# mcu.net
KiCad netlist of a schematic drawn in Altium Designer
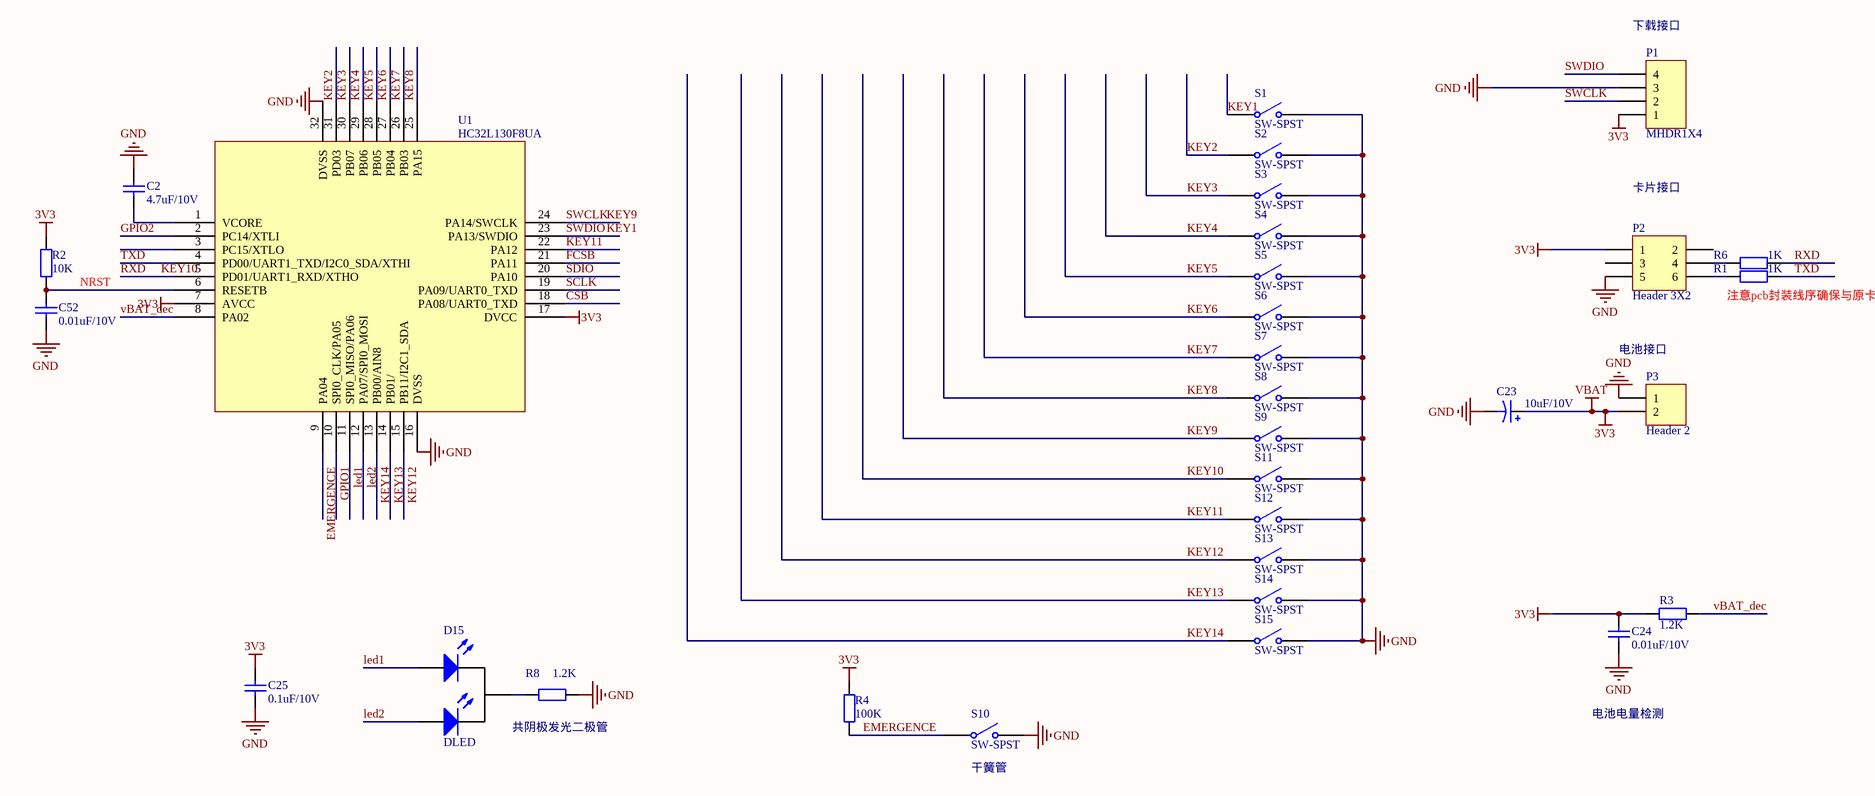
[diagram p0: mcu.SchDoc]

(export (version "E")
  (design (tool "Eeschema 10.0.6"))
  (components
    (comp (ref "C2")
      (value "4.7uF/10V")
      (footprint "0603C")
      (description "Capacitor")
      (fields (field (name "PUBLISHER") "Altium Limited"))
      (libsource (lib "Miscellaneous Devices") (part "Cap"))
    )
    (comp (ref "C23")
      (value "10uF/10V")
      (description "Polarized Capacitor (Radial)")
      (fields (field (name "PUBLISHER") "Altium Limited"))
      (libsource (lib "Miscellaneous Devices") (part "Cap Pol1"))
    )
    (comp (ref "C24")
      (value "0.01uF/10V")
      (footprint "0603C")
      (description "Capacitor")
      (fields (field (name "PUBLISHER") "Altium Limited"))
      (libsource (lib "Miscellaneous Devices") (part "Cap"))
    )
    (comp (ref "C25")
      (value "0.1uF/10V")
      (footprint "0603C")
      (description "Capacitor")
      (fields (field (name "PUBLISHER") "Altium Limited"))
      (libsource (lib "Miscellaneous Devices") (part "Cap"))
    )
    (comp (ref "C52")
      (value "0.01uF/10V")
      (footprint "0603C")
      (description "Capacitor")
      (fields (field (name "PUBLISHER") "Altium Limited"))
      (libsource (lib "Miscellaneous Devices") (part "Cap"))
    )
    (comp (ref "D15") (value "DLED") (libsource (lib "Schlib_20110825") (part "DLED")))
    (comp (ref "P1")
      (value "MHDR1X4")
      (footprint "SIP4")
      (description "Header, 4-Pin")
      (fields (field (name "PUBLISHER") "Altium Limited"))
      (libsource (lib "Miscellaneous Connectors") (part "MHDR1X4"))
    )
    (comp (ref "P2")
      (value "Header 3X2")
      (description "Header, 3-Pin, Dual row")
      (fields (field (name "PUBLISHER") "Altium Limited"))
      (libsource (lib "Miscellaneous Connectors") (part "Header 3X2"))
    )
    (comp (ref "P3")
      (value "Header 2")
      (description "Header, 2-Pin")
      (fields (field (name "PUBLISHER") "Altium Limited"))
      (libsource (lib "Miscellaneous Connectors") (part "Header 2"))
    )
    (comp (ref "R1")
      (value "1K")
      (footprint "0603R")
      (description "Resistor")
      (fields (field (name "PUBLISHER") "Altium Limited"))
      (libsource (lib "Miscellaneous Devices") (part "Res2"))
    )
    (comp (ref "R2")
      (value "10K")
      (footprint "0603R")
      (description "Resistor")
      (fields (field (name "PUBLISHER") "Altium Limited"))
      (libsource (lib "") (part "Res2_2"))
    )
    (comp (ref "R3")
      (value "1.2K")
      (footprint "0603R")
      (description "Resistor")
      (fields (field (name "PUBLISHER") "Altium Limited"))
      (libsource (lib "Miscellaneous Devices") (part "Res2"))
    )
    (comp (ref "R4")
      (value "100K")
      (footprint "0603R")
      (description "Resistor")
      (fields (field (name "PUBLISHER") "Altium Limited"))
      (libsource (lib "") (part "Res2_1"))
    )
    (comp (ref "R6")
      (value "1K")
      (footprint "0603R")
      (description "Resistor")
      (fields (field (name "PUBLISHER") "Altium Limited"))
      (libsource (lib "Miscellaneous Devices") (part "Res2"))
    )
    (comp (ref "R8")
      (value "1.2K")
      (footprint "0603R")
      (description "Resistor")
      (fields (field (name "PUBLISHER") "Altium Limited"))
      (libsource (lib "Miscellaneous Devices") (part "Res2"))
    )
    (comp (ref "S1")
      (value "SW-SPST")
      (description "Single-Pole, Single-Throw Switch")
      (fields (field (name "PUBLISHER") "Altium Limited"))
      (libsource (lib "Miscellaneous Devices") (part "SW-SPST"))
    )
    (comp (ref "S2")
      (value "SW-SPST")
      (description "Single-Pole, Single-Throw Switch")
      (fields (field (name "PUBLISHER") "Altium Limited"))
      (libsource (lib "Miscellaneous Devices") (part "SW-SPST"))
    )
    (comp (ref "S3")
      (value "SW-SPST")
      (description "Single-Pole, Single-Throw Switch")
      (fields (field (name "PUBLISHER") "Altium Limited"))
      (libsource (lib "Miscellaneous Devices") (part "SW-SPST"))
    )
    (comp (ref "S4")
      (value "SW-SPST")
      (description "Single-Pole, Single-Throw Switch")
      (fields (field (name "PUBLISHER") "Altium Limited"))
      (libsource (lib "Miscellaneous Devices") (part "SW-SPST"))
    )
    (comp (ref "S5")
      (value "SW-SPST")
      (description "Single-Pole, Single-Throw Switch")
      (fields (field (name "PUBLISHER") "Altium Limited"))
      (libsource (lib "Miscellaneous Devices") (part "SW-SPST"))
    )
    (comp (ref "S6")
      (value "SW-SPST")
      (description "Single-Pole, Single-Throw Switch")
      (fields (field (name "PUBLISHER") "Altium Limited"))
      (libsource (lib "Miscellaneous Devices") (part "SW-SPST"))
    )
    (comp (ref "S7")
      (value "SW-SPST")
      (description "Single-Pole, Single-Throw Switch")
      (fields (field (name "PUBLISHER") "Altium Limited"))
      (libsource (lib "Miscellaneous Devices") (part "SW-SPST"))
    )
    (comp (ref "S8")
      (value "SW-SPST")
      (description "Single-Pole, Single-Throw Switch")
      (fields (field (name "PUBLISHER") "Altium Limited"))
      (libsource (lib "Miscellaneous Devices") (part "SW-SPST"))
    )
    (comp (ref "S9")
      (value "SW-SPST")
      (description "Single-Pole, Single-Throw Switch")
      (fields (field (name "PUBLISHER") "Altium Limited"))
      (libsource (lib "Miscellaneous Devices") (part "SW-SPST"))
    )
    (comp (ref "S10")
      (value "SW-SPST")
      (description "Single-Pole, Single-Throw Switch")
      (fields (field (name "PUBLISHER") "Altium Limited"))
      (libsource (lib "Miscellaneous Devices") (part "SW-SPST"))
    )
    (comp (ref "S11")
      (value "SW-SPST")
      (description "Single-Pole, Single-Throw Switch")
      (fields (field (name "PUBLISHER") "Altium Limited"))
      (libsource (lib "Miscellaneous Devices") (part "SW-SPST"))
    )
    (comp (ref "S12")
      (value "SW-SPST")
      (description "Single-Pole, Single-Throw Switch")
      (fields (field (name "PUBLISHER") "Altium Limited"))
      (libsource (lib "Miscellaneous Devices") (part "SW-SPST"))
    )
    (comp (ref "S13")
      (value "SW-SPST")
      (description "Single-Pole, Single-Throw Switch")
      (fields (field (name "PUBLISHER") "Altium Limited"))
      (libsource (lib "Miscellaneous Devices") (part "SW-SPST"))
    )
    (comp (ref "S14")
      (value "SW-SPST")
      (description "Single-Pole, Single-Throw Switch")
      (fields (field (name "PUBLISHER") "Altium Limited"))
      (libsource (lib "Miscellaneous Devices") (part "SW-SPST"))
    )
    (comp (ref "S15")
      (value "SW-SPST")
      (description "Single-Pole, Single-Throw Switch")
      (fields (field (name "PUBLISHER") "Altium Limited"))
      (libsource (lib "Miscellaneous Devices") (part "SW-SPST"))
    )
    (comp (ref "U1")
      (value "HC32L130F8UA")
      (footprint "QFN40P400X400X80-32N")
      (libsource (lib "Schlib_20110825") (part "HC32L130F8UA"))
    )
  )
  (nets
    (net (code "1") (name "/CSB") (class "Default")
      (node (ref "U1") (pin "18") (pinfunction "PA08/UART0_TXD_18") (pintype "passive"))
    )
    (net (code "2") (name "/EMERGENCE") (class "Default")
      (node (ref "R4") (pin "2") (pinfunction "2_2") (pintype "passive"))
      (node (ref "S10") (pin "1") (pinfunction "COMMON_1") (pintype "passive"))
      (node (ref "U1") (pin "9") (pinfunction "PA04_9") (pintype "passive"))
    )
    (net (code "3") (name "/FCSB") (class "Default")
      (node (ref "U1") (pin "21") (pinfunction "PA11_21") (pintype "passive"))
    )
    (net (code "4") (name "/GPIO1") (class "Default")
      (node (ref "U1") (pin "10") (pinfunction "SPI0_CLK/PA05_10") (pintype "passive"))
    )
    (net (code "5") (name "/GPIO2") (class "Default")
      (node (ref "U1") (pin "2") (pinfunction "PC14/XTLI_2") (pintype "passive"))
    )
    (net (code "6") (name "/KEY1") (class "Default")
      (node (ref "P1") (pin "4") (pinfunction "4_4") (pintype "passive"))
      (node (ref "S1") (pin "1") (pinfunction "COMMON_1") (pintype "passive"))
      (node (ref "U1") (pin "23") (pinfunction "PA13/SWDIO_23") (pintype "passive"))
    )
    (net (code "7") (name "/KEY2") (class "Default")
      (node (ref "S2") (pin "1") (pinfunction "COMMON_1") (pintype "passive"))
      (node (ref "U1") (pin "31") (pinfunction "PD03_31") (pintype "passive"))
    )
    (net (code "8") (name "/KEY3") (class "Default")
      (node (ref "S3") (pin "1") (pinfunction "COMMON_1") (pintype "passive"))
      (node (ref "U1") (pin "30") (pinfunction "PB07_30") (pintype "passive"))
    )
    (net (code "9") (name "/KEY4") (class "Default")
      (node (ref "S4") (pin "1") (pinfunction "COMMON_1") (pintype "passive"))
      (node (ref "U1") (pin "29") (pinfunction "PB06_29") (pintype "passive"))
    )
    (net (code "10") (name "/KEY5") (class "Default")
      (node (ref "S5") (pin "1") (pinfunction "COMMON_1") (pintype "passive"))
      (node (ref "U1") (pin "28") (pinfunction "PB05_28") (pintype "passive"))
    )
    (net (code "11") (name "/KEY6") (class "Default")
      (node (ref "S6") (pin "1") (pinfunction "COMMON_1") (pintype "passive"))
      (node (ref "U1") (pin "27") (pinfunction "PB04_27") (pintype "passive"))
    )
    (net (code "12") (name "/KEY7") (class "Default")
      (node (ref "S7") (pin "1") (pinfunction "COMMON_1") (pintype "passive"))
      (node (ref "U1") (pin "26") (pinfunction "PB03_26") (pintype "passive"))
    )
    (net (code "13") (name "/KEY8") (class "Default")
      (node (ref "S8") (pin "1") (pinfunction "COMMON_1") (pintype "passive"))
      (node (ref "U1") (pin "25") (pinfunction "PA15_25") (pintype "passive"))
    )
    (net (code "14") (name "/KEY9") (class "Default")
      (node (ref "P1") (pin "2") (pinfunction "2_2") (pintype "passive"))
      (node (ref "S9") (pin "1") (pinfunction "COMMON_1") (pintype "passive"))
      (node (ref "U1") (pin "24") (pinfunction "PA14/SWCLK_24") (pintype "passive"))
    )
    (net (code "15") (name "/KEY10") (class "Default")
      (node (ref "R6") (pin "1") (pinfunction "1_1") (pintype "passive"))
      (node (ref "S11") (pin "1") (pinfunction "COMMON_1") (pintype "passive"))
      (node (ref "U1") (pin "5") (pinfunction "PD01/UART1_RXD/XTHO_5") (pintype "passive"))
    )
    (net (code "16") (name "/KEY11") (class "Default")
      (node (ref "S12") (pin "1") (pinfunction "COMMON_1") (pintype "passive"))
      (node (ref "U1") (pin "22") (pinfunction "PA12_22") (pintype "passive"))
    )
    (net (code "17") (name "/KEY12") (class "Default")
      (node (ref "S13") (pin "1") (pinfunction "COMMON_1") (pintype "passive"))
      (node (ref "U1") (pin "15") (pinfunction "PB11/I2C1_SDA_15") (pintype "passive"))
    )
    (net (code "18") (name "/KEY13") (class "Default")
      (node (ref "S14") (pin "1") (pinfunction "COMMON_1") (pintype "passive"))
      (node (ref "U1") (pin "14") (pinfunction "PB01/_14") (pintype "passive"))
    )
    (net (code "19") (name "/KEY14") (class "Default")
      (node (ref "S15") (pin "1") (pinfunction "COMMON_1") (pintype "passive"))
      (node (ref "U1") (pin "13") (pinfunction "PB00/AIN8_13") (pintype "passive"))
    )
    (net (code "20") (name "/NRST") (class "Default")
      (node (ref "C52") (pin "1") (pinfunction "1_1") (pintype "passive"))
      (node (ref "R2") (pin "1") (pinfunction "1_1") (pintype "passive"))
      (node (ref "U1") (pin "6") (pinfunction "RESETB_6") (pintype "passive"))
    )
    (net (code "21") (name "/SCLK") (class "Default")
      (node (ref "U1") (pin "19") (pinfunction "PA09/UART0_TXD_19") (pintype "passive"))
    )
    (net (code "22") (name "/SDIO") (class "Default")
      (node (ref "U1") (pin "20") (pinfunction "PA10_20") (pintype "passive"))
    )
    (net (code "23") (name "/TXD") (class "Default")
      (node (ref "R1") (pin "1") (pinfunction "1_1") (pintype "passive"))
      (node (ref "U1") (pin "4") (pinfunction "PD00/UART1_TXD/I2C0_SDA/XTHI_4") (pintype "passive"))
    )
    (net (code "24") (name "/led1") (class "Default")
      (node (ref "D15") (pin "1") (pinfunction "A_1") (pintype "passive"))
      (node (ref "U1") (pin "11") (pinfunction "SPI0_MISO/PA06_11") (pintype "passive"))
    )
    (net (code "25") (name "/led2") (class "Default")
      (node (ref "D15") (pin "3") (pinfunction "A_3") (pintype "passive"))
      (node (ref "U1") (pin "12") (pinfunction "PA07/SPI0_MOSI_12") (pintype "passive"))
    )
    (net (code "26") (name "/vBAT_dec") (class "Default")
      (node (ref "R3") (pin "1") (pinfunction "1_1") (pintype "passive"))
      (node (ref "U1") (pin "8") (pinfunction "PA02_8") (pintype "passive"))
    )
    (net (code "27") (name "3V3") (class "Default")
      (node (ref "C23") (pin "1") (pinfunction "1_1") (pintype "passive"))
      (node (ref "C24") (pin "1") (pinfunction "1_1") (pintype "passive"))
      (node (ref "C25") (pin "1") (pinfunction "1_1") (pintype "passive"))
      (node (ref "P1") (pin "1") (pinfunction "1_1") (pintype "passive"))
      (node (ref "P2") (pin "1") (pinfunction "1_1") (pintype "passive"))
      (node (ref "P3") (pin "2") (pinfunction "2_2") (pintype "passive"))
      (node (ref "R2") (pin "2") (pinfunction "2_2") (pintype "passive"))
      (node (ref "R3") (pin "2") (pinfunction "2_2") (pintype "passive"))
      (node (ref "R4") (pin "1") (pinfunction "1_1") (pintype "passive"))
      (node (ref "U1") (pin "17") (pinfunction "DVCC_17") (pintype "passive"))
      (node (ref "U1") (pin "7") (pinfunction "AVCC_7") (pintype "passive"))
    )
    (net (code "28") (name "GND") (class "Default")
      (node (ref "C2") (pin "1") (pinfunction "1_1") (pintype "passive"))
      (node (ref "C23") (pin "2") (pinfunction "2_2") (pintype "passive"))
      (node (ref "C24") (pin "2") (pinfunction "2_2") (pintype "passive"))
      (node (ref "C25") (pin "2") (pinfunction "2_2") (pintype "passive"))
      (node (ref "C52") (pin "2") (pinfunction "2_2") (pintype "passive"))
      (node (ref "P1") (pin "3") (pinfunction "3_3") (pintype "passive"))
      (node (ref "P2") (pin "5") (pinfunction "5_5") (pintype "passive"))
      (node (ref "P3") (pin "1") (pinfunction "1_1") (pintype "passive"))
      (node (ref "R8") (pin "1") (pinfunction "1_1") (pintype "passive"))
      (node (ref "S1") (pin "2") (pinfunction "NO_2") (pintype "passive"))
      (node (ref "S10") (pin "2") (pinfunction "NO_2") (pintype "passive"))
      (node (ref "S11") (pin "2") (pinfunction "NO_2") (pintype "passive"))
      (node (ref "S12") (pin "2") (pinfunction "NO_2") (pintype "passive"))
      (node (ref "S13") (pin "2") (pinfunction "NO_2") (pintype "passive"))
      (node (ref "S14") (pin "2") (pinfunction "NO_2") (pintype "passive"))
      (node (ref "S15") (pin "2") (pinfunction "NO_2") (pintype "passive"))
      (node (ref "S2") (pin "2") (pinfunction "NO_2") (pintype "passive"))
      (node (ref "S3") (pin "2") (pinfunction "NO_2") (pintype "passive"))
      (node (ref "S4") (pin "2") (pinfunction "NO_2") (pintype "passive"))
      (node (ref "S5") (pin "2") (pinfunction "NO_2") (pintype "passive"))
      (node (ref "S6") (pin "2") (pinfunction "NO_2") (pintype "passive"))
      (node (ref "S7") (pin "2") (pinfunction "NO_2") (pintype "passive"))
      (node (ref "S8") (pin "2") (pinfunction "NO_2") (pintype "passive"))
      (node (ref "S9") (pin "2") (pinfunction "NO_2") (pintype "passive"))
      (node (ref "U1") (pin "16") (pinfunction "DVSS_16") (pintype "passive"))
      (node (ref "U1") (pin "32") (pinfunction "DVSS_32") (pintype "passive"))
    )
    (net (code "29") (name "Net-(D15-K)") (class "Default")
      (node (ref "D15") (pin "2") (pinfunction "K_2") (pintype "passive"))
      (node (ref "R8") (pin "2") (pinfunction "2_2") (pintype "passive"))
    )
    (net (code "30") (name "Net-(P2-Pad4)") (class "Default")
      (node (ref "P2") (pin "4") (pinfunction "4_4") (pintype "passive"))
      (node (ref "R6") (pin "2") (pinfunction "2_2") (pintype "passive"))
    )
    (net (code "31") (name "Net-(P2-Pad6)") (class "Default")
      (node (ref "P2") (pin "6") (pinfunction "6_6") (pintype "passive"))
      (node (ref "R1") (pin "2") (pinfunction "2_2") (pintype "passive"))
    )
    (net (code "32") (name "Net-(U1-VCORE)") (class "Default")
      (node (ref "C2") (pin "2") (pinfunction "2_2") (pintype "passive"))
      (node (ref "U1") (pin "1") (pinfunction "VCORE_1") (pintype "passive"))
    )
    (net (code "33") (name "unconnected-(P2-Pad2)") (class "Default")
      (node (ref "P2") (pin "2") (pinfunction "2_2") (pintype "passive"))
    )
    (net (code "34") (name "unconnected-(P2-Pad3)") (class "Default")
      (node (ref "P2") (pin "3") (pinfunction "3_3") (pintype "passive"))
    )
    (net (code "35") (name "unconnected-(U1-PC15{slash}XTLO-Pad3)") (class "Default")
      (node (ref "U1") (pin "3") (pinfunction "PC15/XTLO_3") (pintype "passive"))
    )
  )
)
